# S7CAS-PLEIADES-CARTE-MERE_Pxx_CAN.net
KiCad netlist of a schematic drawn in Altium Designer
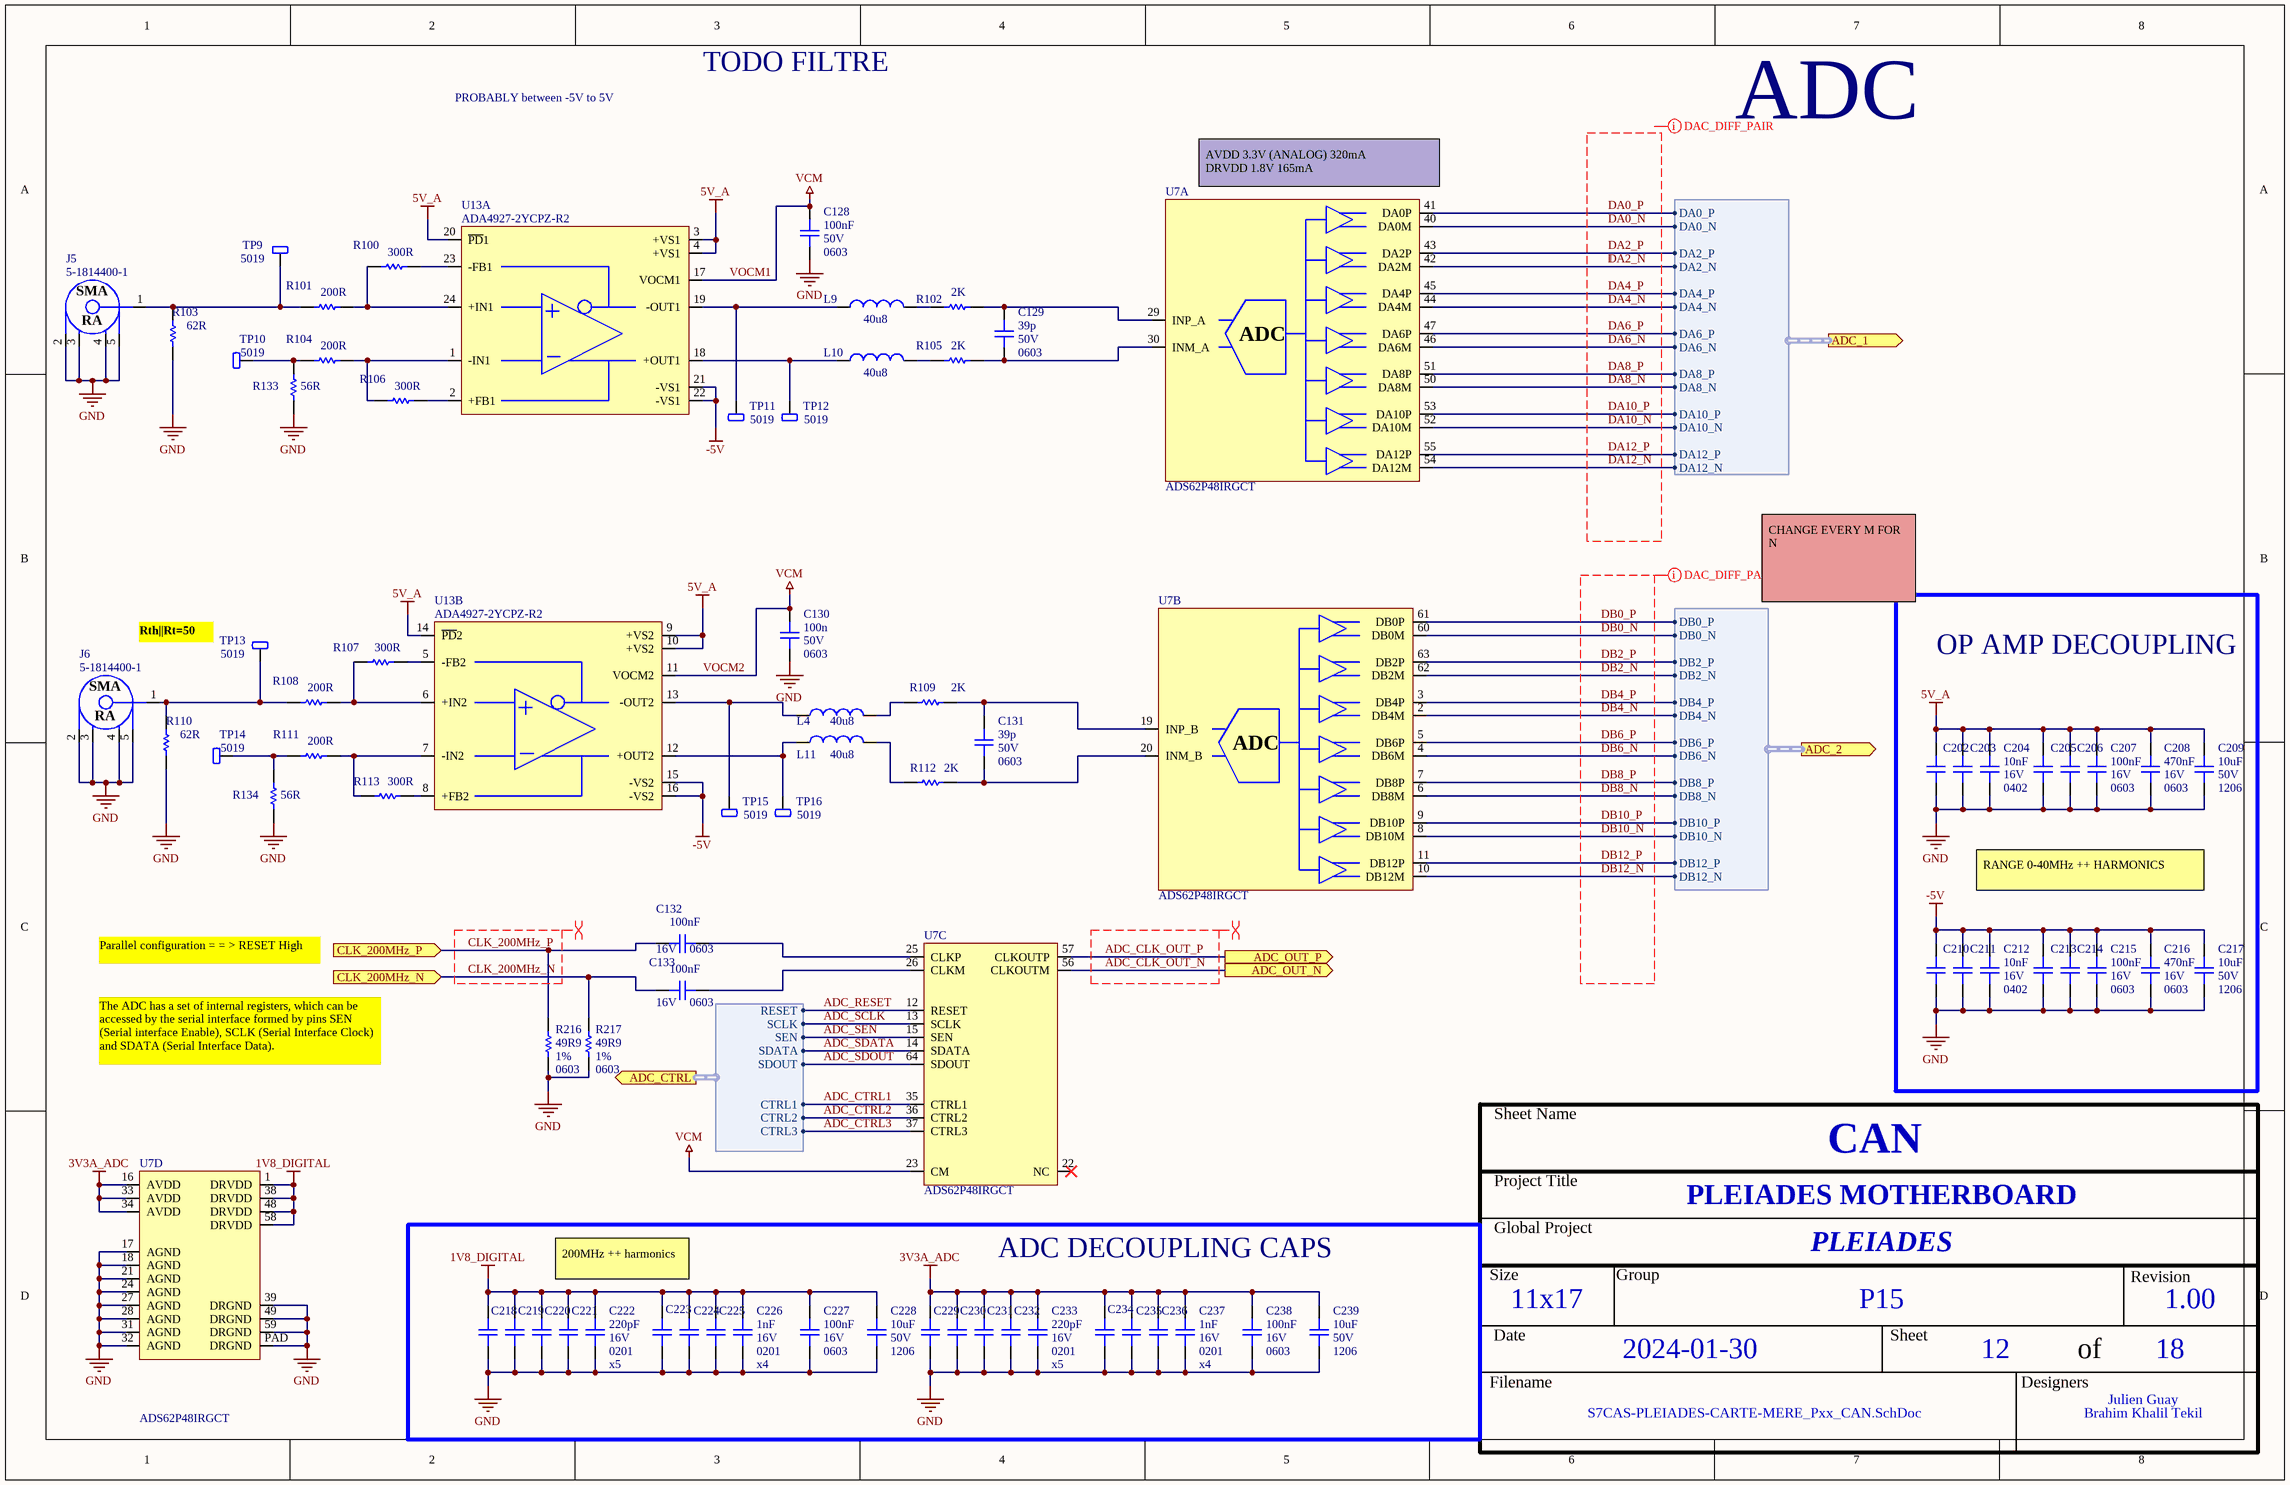
[diagram p0: S7CAS-PLEIADES-CARTE-MERE_Pxx_CAN.SchDoc]

(export (version "E")
  (design (tool "Eeschema 10.0.6"))
  (components
    (comp (ref "C128")
      (value "100nF")
      (footprint "CAP_0603")
      (description "CAP - 0603")
      (fields
        (field (name "VOLTAGE") "50V")
        (field (name "PACKAGE") "0603")
        (field (name "CREATEDBY") "Jonathan Bouchard")
      )
      (libsource (lib "S7CAS_LIB2023") (part "CAP - 0603"))
    )
    (comp (ref "C129")
      (value "39p")
      (footprint "CAP_0603")
      (description "CAP - 0603")
      (fields
        (field (name "VOLTAGE") "50V")
        (field (name "PACKAGE") "0603")
        (field (name "CREATEDBY") "Jonathan Bouchard")
      )
      (libsource (lib "S7CAS_LIB2023") (part "CAP - 0603"))
    )
    (comp (ref "C130")
      (value "100n")
      (footprint "CAP_0603")
      (description "CAP - 0603")
      (fields
        (field (name "VOLTAGE") "50V")
        (field (name "PACKAGE") "0603")
        (field (name "CREATEDBY") "Jonathan Bouchard")
      )
      (libsource (lib "S7CAS_LIB2023") (part "CAP - 0603"))
    )
    (comp (ref "C131")
      (value "39p")
      (footprint "CAP_0603")
      (description "CAP - 0603")
      (fields
        (field (name "VOLTAGE") "50V")
        (field (name "PACKAGE") "0603")
        (field (name "CREATEDBY") "Jonathan Bouchard")
      )
      (libsource (lib "S7CAS_LIB2023") (part "CAP - 0603"))
    )
    (comp (ref "C132")
      (value "100nF")
      (footprint "CAP_0603")
      (description "CAP - 0603")
      (fields
        (field (name "VOLTAGE") "16V")
        (field (name "PACKAGE") "0603")
        (field (name "CREATEDBY") "Jonathan Bouchard")
      )
      (libsource (lib "S7CAS_LIB2023") (part "CAP - 0603"))
    )
    (comp (ref "C133")
      (value "100nF")
      (footprint "CAP_0603")
      (description "CAP - 0603")
      (fields
        (field (name "VOLTAGE") "16V")
        (field (name "PACKAGE") "0603")
        (field (name "CREATEDBY") "Jonathan Bouchard")
      )
      (libsource (lib "S7CAS_LIB2023") (part "CAP - 0603"))
    )
    (comp (ref "C202")
      (value "CAP - 0402")
      (footprint "CAP_0402")
      (fields (field (name "VOLTAGE") "16V") (field (name "CREATEDBY") "Jonathan Bouchard"))
      (libsource (lib "S7CAS_LIB2023") (part "CAP - 0402"))
    )
    (comp (ref "C203")
      (value "CAP - 0402")
      (footprint "CAP_0402")
      (fields (field (name "VOLTAGE") "16V") (field (name "CREATEDBY") "Jonathan Bouchard"))
      (libsource (lib "S7CAS_LIB2023") (part "CAP - 0402"))
    )
    (comp (ref "C204")
      (value "10nF")
      (footprint "CAP_0402")
      (description "CAP - 0402")
      (fields
        (field (name "VOLTAGE") "16V")
        (field (name "PACKAGE") "0402")
        (field (name "CREATEDBY") "Jonathan Bouchard")
      )
      (libsource (lib "S7CAS_LIB2023") (part "CAP - 0402"))
    )
    (comp (ref "C205")
      (value "CAP - 0603")
      (footprint "CAP_0603")
      (fields (field (name "VOLTAGE") "16V") (field (name "CREATEDBY") "Jonathan Bouchard"))
      (libsource (lib "S7CAS_LIB2023") (part "CAP - 0603"))
    )
    (comp (ref "C206")
      (value "CAP - 0603")
      (footprint "CAP_0603")
      (fields (field (name "VOLTAGE") "16V") (field (name "CREATEDBY") "Jonathan Bouchard"))
      (libsource (lib "S7CAS_LIB2023") (part "CAP - 0603"))
    )
    (comp (ref "C207")
      (value "100nF")
      (footprint "CAP_0603")
      (description "CAP - 0603")
      (fields
        (field (name "VOLTAGE") "16V")
        (field (name "PACKAGE") "0603")
        (field (name "CREATEDBY") "Jonathan Bouchard")
      )
      (libsource (lib "S7CAS_LIB2023") (part "CAP - 0603"))
    )
    (comp (ref "C208")
      (value "470nF")
      (footprint "CAP_0603")
      (description "CAP - 0603")
      (fields
        (field (name "VOLTAGE") "16V")
        (field (name "PACKAGE") "0603")
        (field (name "CREATEDBY") "Jonathan Bouchard")
      )
      (libsource (lib "S7CAS_LIB2023") (part "CAP - 0603"))
    )
    (comp (ref "C209")
      (value "10uF")
      (footprint "CAP_1206")
      (description "CAP - 1206")
      (fields
        (field (name "VOLTAGE") "50V")
        (field (name "PACKAGE") "1206")
        (field (name "CREATEDBY") "Jonathan Bouchard")
      )
      (libsource (lib "S7CAS_LIB2023") (part "CAP - 1206"))
    )
    (comp (ref "C210")
      (value "CAP - 0402")
      (footprint "CAP_0402")
      (fields (field (name "VOLTAGE") "16V") (field (name "CREATEDBY") "Jonathan Bouchard"))
      (libsource (lib "S7CAS_LIB2023") (part "CAP - 0402"))
    )
    (comp (ref "C211")
      (value "CAP - 0402")
      (footprint "CAP_0402")
      (fields (field (name "VOLTAGE") "16V") (field (name "CREATEDBY") "Jonathan Bouchard"))
      (libsource (lib "S7CAS_LIB2023") (part "CAP - 0402"))
    )
    (comp (ref "C212")
      (value "10nF")
      (footprint "CAP_0402")
      (description "CAP - 0402")
      (fields
        (field (name "VOLTAGE") "16V")
        (field (name "PACKAGE") "0402")
        (field (name "CREATEDBY") "Jonathan Bouchard")
      )
      (libsource (lib "S7CAS_LIB2023") (part "CAP - 0402"))
    )
    (comp (ref "C213")
      (value "CAP - 0603")
      (footprint "CAP_0603")
      (fields (field (name "VOLTAGE") "16V") (field (name "CREATEDBY") "Jonathan Bouchard"))
      (libsource (lib "S7CAS_LIB2023") (part "CAP - 0603"))
    )
    (comp (ref "C214")
      (value "CAP - 0603")
      (footprint "CAP_0603")
      (fields (field (name "VOLTAGE") "16V") (field (name "CREATEDBY") "Jonathan Bouchard"))
      (libsource (lib "S7CAS_LIB2023") (part "CAP - 0603"))
    )
    (comp (ref "C215")
      (value "100nF")
      (footprint "CAP_0603")
      (description "CAP - 0603")
      (fields
        (field (name "VOLTAGE") "16V")
        (field (name "PACKAGE") "0603")
        (field (name "CREATEDBY") "Jonathan Bouchard")
      )
      (libsource (lib "S7CAS_LIB2023") (part "CAP - 0603"))
    )
    (comp (ref "C216")
      (value "470nF")
      (footprint "CAP_0603")
      (description "CAP - 0603")
      (fields
        (field (name "VOLTAGE") "16V")
        (field (name "PACKAGE") "0603")
        (field (name "CREATEDBY") "Jonathan Bouchard")
      )
      (libsource (lib "S7CAS_LIB2023") (part "CAP - 0603"))
    )
    (comp (ref "C217")
      (value "10uF")
      (footprint "CAP_1206")
      (description "CAP - 1206")
      (fields
        (field (name "VOLTAGE") "50V")
        (field (name "PACKAGE") "1206")
        (field (name "CREATEDBY") "Jonathan Bouchard")
      )
      (libsource (lib "S7CAS_LIB2023") (part "CAP - 1206"))
    )
    (comp (ref "C218")
      (value "CAP - 0201")
      (footprint "CAP_0201")
      (fields (field (name "VOLTAGE") "16V") (field (name "CREATEDBY") "Jonathan Bouchard"))
      (libsource (lib "S7CAS_LIB2023") (part "CAP - 0201"))
    )
    (comp (ref "C219")
      (value "CAP - 0201")
      (footprint "CAP_0201")
      (fields (field (name "VOLTAGE") "16V") (field (name "CREATEDBY") "Jonathan Bouchard"))
      (libsource (lib "S7CAS_LIB2023") (part "CAP - 0201"))
    )
    (comp (ref "C220")
      (value "CAP - 0201")
      (footprint "CAP_0201")
      (fields (field (name "VOLTAGE") "16V") (field (name "CREATEDBY") "Jonathan Bouchard"))
      (libsource (lib "S7CAS_LIB2023") (part "CAP - 0201"))
    )
    (comp (ref "C221")
      (value "CAP - 0201")
      (footprint "CAP_0201")
      (fields (field (name "VOLTAGE") "16V") (field (name "CREATEDBY") "Jonathan Bouchard"))
      (libsource (lib "S7CAS_LIB2023") (part "CAP - 0201"))
    )
    (comp (ref "C222")
      (value "220pF")
      (footprint "CAP_0201")
      (description "CAP - 0201")
      (fields
        (field (name "VOLTAGE") "16V")
        (field (name "PACKAGE") "0201")
        (field (name "CREATEDBY") "Jonathan Bouchard")
      )
      (libsource (lib "S7CAS_LIB2023") (part "CAP - 0201"))
    )
    (comp (ref "C223")
      (value "CAP - 0201")
      (footprint "CAP_0201")
      (fields (field (name "VOLTAGE") "16V") (field (name "CREATEDBY") "Jonathan Bouchard"))
      (libsource (lib "S7CAS_LIB2023") (part "CAP - 0201"))
    )
    (comp (ref "C224")
      (value "CAP - 0201")
      (footprint "CAP_0201")
      (fields (field (name "VOLTAGE") "16V") (field (name "CREATEDBY") "Jonathan Bouchard"))
      (libsource (lib "S7CAS_LIB2023") (part "CAP - 0201"))
    )
    (comp (ref "C225")
      (value "CAP - 0201")
      (footprint "CAP_0201")
      (fields (field (name "VOLTAGE") "16V") (field (name "CREATEDBY") "Jonathan Bouchard"))
      (libsource (lib "S7CAS_LIB2023") (part "CAP - 0201"))
    )
    (comp (ref "C226")
      (value "1nF")
      (footprint "CAP_0201")
      (description "CAP - 0201")
      (fields
        (field (name "VOLTAGE") "16V")
        (field (name "PACKAGE") "0201")
        (field (name "CREATEDBY") "Jonathan Bouchard")
      )
      (libsource (lib "S7CAS_LIB2023") (part "CAP - 0201"))
    )
    (comp (ref "C227")
      (value "100nF")
      (footprint "CAP_0603")
      (description "CAP - 0603")
      (fields
        (field (name "VOLTAGE") "16V")
        (field (name "PACKAGE") "0603")
        (field (name "CREATEDBY") "Jonathan Bouchard")
      )
      (libsource (lib "S7CAS_LIB2023") (part "CAP - 0603"))
    )
    (comp (ref "C228")
      (value "10uF")
      (footprint "CAP_1206")
      (description "CAP - 1206")
      (fields
        (field (name "VOLTAGE") "50V")
        (field (name "PACKAGE") "1206")
        (field (name "CREATEDBY") "Jonathan Bouchard")
      )
      (libsource (lib "S7CAS_LIB2023") (part "CAP - 1206"))
    )
    (comp (ref "C229")
      (value "CAP - 0201")
      (footprint "CAP_0201")
      (fields (field (name "VOLTAGE") "16V") (field (name "CREATEDBY") "Jonathan Bouchard"))
      (libsource (lib "S7CAS_LIB2023") (part "CAP - 0201"))
    )
    (comp (ref "C230")
      (value "CAP - 0201")
      (footprint "CAP_0201")
      (fields (field (name "VOLTAGE") "16V") (field (name "CREATEDBY") "Jonathan Bouchard"))
      (libsource (lib "S7CAS_LIB2023") (part "CAP - 0201"))
    )
    (comp (ref "C231")
      (value "CAP - 0201")
      (footprint "CAP_0201")
      (fields (field (name "VOLTAGE") "16V") (field (name "CREATEDBY") "Jonathan Bouchard"))
      (libsource (lib "S7CAS_LIB2023") (part "CAP - 0201"))
    )
    (comp (ref "C232")
      (value "CAP - 0201")
      (footprint "CAP_0201")
      (fields (field (name "VOLTAGE") "16V") (field (name "CREATEDBY") "Jonathan Bouchard"))
      (libsource (lib "S7CAS_LIB2023") (part "CAP - 0201"))
    )
    (comp (ref "C233")
      (value "220pF")
      (footprint "CAP_0201")
      (description "CAP - 0201")
      (fields
        (field (name "VOLTAGE") "16V")
        (field (name "PACKAGE") "0201")
        (field (name "CREATEDBY") "Jonathan Bouchard")
      )
      (libsource (lib "S7CAS_LIB2023") (part "CAP - 0201"))
    )
    (comp (ref "C234")
      (value "CAP - 0201")
      (footprint "CAP_0201")
      (fields (field (name "VOLTAGE") "16V") (field (name "CREATEDBY") "Jonathan Bouchard"))
      (libsource (lib "S7CAS_LIB2023") (part "CAP - 0201"))
    )
    (comp (ref "C235")
      (value "CAP - 0201")
      (footprint "CAP_0201")
      (fields (field (name "VOLTAGE") "16V") (field (name "CREATEDBY") "Jonathan Bouchard"))
      (libsource (lib "S7CAS_LIB2023") (part "CAP - 0201"))
    )
    (comp (ref "C236")
      (value "CAP - 0201")
      (footprint "CAP_0201")
      (fields (field (name "VOLTAGE") "16V") (field (name "CREATEDBY") "Jonathan Bouchard"))
      (libsource (lib "S7CAS_LIB2023") (part "CAP - 0201"))
    )
    (comp (ref "C237")
      (value "1nF")
      (footprint "CAP_0201")
      (description "CAP - 0201")
      (fields
        (field (name "VOLTAGE") "16V")
        (field (name "PACKAGE") "0201")
        (field (name "CREATEDBY") "Jonathan Bouchard")
      )
      (libsource (lib "S7CAS_LIB2023") (part "CAP - 0201"))
    )
    (comp (ref "C238")
      (value "100nF")
      (footprint "CAP_0603")
      (description "CAP - 0603")
      (fields
        (field (name "VOLTAGE") "16V")
        (field (name "PACKAGE") "0603")
        (field (name "CREATEDBY") "Jonathan Bouchard")
      )
      (libsource (lib "S7CAS_LIB2023") (part "CAP - 0603"))
    )
    (comp (ref "C239")
      (value "10uF")
      (footprint "CAP_1206")
      (description "CAP - 1206")
      (fields
        (field (name "VOLTAGE") "50V")
        (field (name "PACKAGE") "1206")
        (field (name "CREATEDBY") "Jonathan Bouchard")
      )
      (libsource (lib "S7CAS_LIB2023") (part "CAP - 1206"))
    )
    (comp (ref "J5")
      (value "5-1814400-1")
      (footprint "CONN_SMA_5-1814400-1")
      (description "CONN -  SMA JACK R/A 50 OHM - TH")
      (fields
        (field (name "MFG") "TE Connectivity AMP Connectors")
        (field (name "CREATEDBY") "Jonathan Bouchard")
      )
      (libsource (lib "S7CAS_LIB2023") (part "CONN_SMA_5-1814400-1"))
    )
    (comp (ref "J6")
      (value "5-1814400-1")
      (footprint "CONN_SMA_5-1814400-1")
      (description "CONN -  SMA JACK R/A 50 OHM - TH")
      (fields
        (field (name "MFG") "TE Connectivity AMP Connectors")
        (field (name "CREATEDBY") "Jonathan Bouchard")
      )
      (libsource (lib "S7CAS_LIB2023") (part "CONN_SMA_5-1814400-1"))
    )
    (comp (ref "L4")
      (value "40u8")
      (footprint "INDUCT_0603")
      (description "INDUCTOR - 0603")
      (libsource (lib "S7CAS_LIB2023") (part "INDUCT - 0603"))
    )
    (comp (ref "L9")
      (value "40u8")
      (footprint "INDUCT_0603")
      (description "INDUCTOR - 0603")
      (libsource (lib "S7CAS_LIB2023") (part "INDUCT - 0603"))
    )
    (comp (ref "L10")
      (value "40u8")
      (footprint "INDUCT_0603")
      (description "INDUCTOR - 0603")
      (libsource (lib "S7CAS_LIB2023") (part "INDUCT - 0603"))
    )
    (comp (ref "L11")
      (value "40u8")
      (footprint "INDUCT_0603")
      (description "INDUCTOR - 0603")
      (libsource (lib "S7CAS_LIB2023") (part "INDUCT - 0603"))
    )
    (comp (ref "R100")
      (value "300R")
      (footprint "RES_0603")
      (description "RES - 0603")
      (fields (field (name "CREATEDBY") "Jonathan Bouchard"))
      (libsource (lib "S7CAS_LIB2023") (part "RES - 0603"))
    )
    (comp (ref "R101")
      (value "200R")
      (footprint "RES_0603")
      (description "RES - 0603")
      (fields (field (name "CREATEDBY") "Jonathan Bouchard"))
      (libsource (lib "S7CAS_LIB2023") (part "RES - 0603"))
    )
    (comp (ref "R102")
      (value "2K")
      (footprint "RES_0603")
      (description "RES - 0603")
      (fields (field (name "CREATEDBY") "Jonathan Bouchard"))
      (libsource (lib "S7CAS_LIB2023") (part "RES - 0603"))
    )
    (comp (ref "R103")
      (value "62R")
      (footprint "RES_0603")
      (description "RES - 0603")
      (fields (field (name "CREATEDBY") "Jonathan Bouchard"))
      (libsource (lib "S7CAS_LIB2023") (part "RES - 0603"))
    )
    (comp (ref "R104")
      (value "200R")
      (footprint "RES_0603")
      (description "RES - 0603")
      (fields (field (name "CREATEDBY") "Jonathan Bouchard"))
      (libsource (lib "S7CAS_LIB2023") (part "RES - 0603"))
    )
    (comp (ref "R105")
      (value "2K")
      (footprint "RES_0603")
      (description "RES - 0603")
      (fields (field (name "CREATEDBY") "Jonathan Bouchard"))
      (libsource (lib "S7CAS_LIB2023") (part "RES - 0603"))
    )
    (comp (ref "R106")
      (value "300R")
      (footprint "RES_0603")
      (description "RES - 0603")
      (fields (field (name "CREATEDBY") "Jonathan Bouchard"))
      (libsource (lib "S7CAS_LIB2023") (part "RES - 0603"))
    )
    (comp (ref "R107")
      (value "300R")
      (footprint "RES_0603")
      (description "RES - 0603")
      (fields (field (name "CREATEDBY") "Jonathan Bouchard"))
      (libsource (lib "S7CAS_LIB2023") (part "RES - 0603"))
    )
    (comp (ref "R108")
      (value "200R")
      (footprint "RES_0603")
      (description "RES - 0603")
      (fields (field (name "CREATEDBY") "Jonathan Bouchard"))
      (libsource (lib "S7CAS_LIB2023") (part "RES - 0603"))
    )
    (comp (ref "R109")
      (value "2K")
      (footprint "RES_0603")
      (description "RES - 0603")
      (fields (field (name "CREATEDBY") "Jonathan Bouchard"))
      (libsource (lib "S7CAS_LIB2023") (part "RES - 0603"))
    )
    (comp (ref "R110")
      (value "62R")
      (footprint "RES_0603")
      (description "RES - 0603")
      (fields (field (name "CREATEDBY") "Jonathan Bouchard"))
      (libsource (lib "S7CAS_LIB2023") (part "RES - 0603"))
    )
    (comp (ref "R111")
      (value "200R")
      (footprint "RES_0603")
      (description "RES - 0603")
      (fields (field (name "CREATEDBY") "Jonathan Bouchard"))
      (libsource (lib "S7CAS_LIB2023") (part "RES - 0603"))
    )
    (comp (ref "R112")
      (value "2K")
      (footprint "RES_0603")
      (description "RES - 0603")
      (fields (field (name "CREATEDBY") "Jonathan Bouchard"))
      (libsource (lib "S7CAS_LIB2023") (part "RES - 0603"))
    )
    (comp (ref "R113")
      (value "300R")
      (footprint "RES_0603")
      (description "RES - 0603")
      (fields (field (name "CREATEDBY") "Jonathan Bouchard"))
      (libsource (lib "S7CAS_LIB2023") (part "RES - 0603"))
    )
    (comp (ref "R133")
      (value "56R")
      (footprint "RES_0603")
      (description "RES - 0603")
      (fields (field (name "CREATEDBY") "Jonathan Bouchard"))
      (libsource (lib "S7CAS_LIB2023") (part "RES - 0603"))
    )
    (comp (ref "R134")
      (value "56R")
      (footprint "RES_0603")
      (description "RES - 0603")
      (fields (field (name "CREATEDBY") "Jonathan Bouchard"))
      (libsource (lib "S7CAS_LIB2023") (part "RES - 0603"))
    )
    (comp (ref "R216")
      (value "49R9")
      (footprint "RES_0603")
      (description "RES - 0603")
      (fields
        (field (name "PACKAGE") "0603")
        (field (name "PRECISION") "1%")
        (field (name "CREATEDBY") "Jonathan Bouchard")
      )
      (libsource (lib "S7CAS_LIB2023") (part "RES - 0603"))
    )
    (comp (ref "R217")
      (value "49R9")
      (footprint "RES_0603")
      (description "RES - 0603")
      (fields
        (field (name "PACKAGE") "0603")
        (field (name "PRECISION") "1%")
        (field (name "CREATEDBY") "Jonathan Bouchard")
      )
      (libsource (lib "S7CAS_LIB2023") (part "RES - 0603"))
    )
    (comp (ref "TP9")
      (value "5019")
      (footprint "TPO_SMD_5019")
      (description "TPO - PC TEST POINT MINI - SMD")
      (fields
        (field (name "CREATEDBY/DATE") "Olivier Bernard / 5/12/2017")
        (field (name "VERIFIEDBY") "Caroline Paulin / 5 juillet 2018")
      )
      (libsource (lib "S7CAS_LIB2023") (part "TPO_SMD_5019"))
    )
    (comp (ref "TP10")
      (value "5019")
      (footprint "TPO_SMD_5019")
      (description "TPO - PC TEST POINT MINI - SMD")
      (fields
        (field (name "CREATEDBY/DATE") "Olivier Bernard / 5/12/2017")
        (field (name "VERIFIEDBY") "Caroline Paulin / 5 juillet 2018")
      )
      (libsource (lib "S7CAS_LIB2023") (part "TPO_SMD_5019"))
    )
    (comp (ref "TP11")
      (value "5019")
      (footprint "TPO_SMD_5019")
      (description "TPO - PC TEST POINT MINI - SMD")
      (fields
        (field (name "CREATEDBY/DATE") "Olivier Bernard / 5/12/2017")
        (field (name "VERIFIEDBY") "Caroline Paulin / 5 juillet 2018")
      )
      (libsource (lib "S7CAS_LIB2023") (part "TPO_SMD_5019"))
    )
    (comp (ref "TP12")
      (value "5019")
      (footprint "TPO_SMD_5019")
      (description "TPO - PC TEST POINT MINI - SMD")
      (fields
        (field (name "CREATEDBY/DATE") "Olivier Bernard / 5/12/2017")
        (field (name "VERIFIEDBY") "Caroline Paulin / 5 juillet 2018")
      )
      (libsource (lib "S7CAS_LIB2023") (part "TPO_SMD_5019"))
    )
    (comp (ref "TP13")
      (value "5019")
      (footprint "TPO_SMD_5019")
      (description "TPO - PC TEST POINT MINI - SMD")
      (fields
        (field (name "CREATEDBY/DATE") "Olivier Bernard / 5/12/2017")
        (field (name "VERIFIEDBY") "Caroline Paulin / 5 juillet 2018")
      )
      (libsource (lib "S7CAS_LIB2023") (part "TPO_SMD_5019"))
    )
    (comp (ref "TP14")
      (value "5019")
      (footprint "TPO_SMD_5019")
      (description "TPO - PC TEST POINT MINI - SMD")
      (fields
        (field (name "CREATEDBY/DATE") "Olivier Bernard / 5/12/2017")
        (field (name "VERIFIEDBY") "Caroline Paulin / 5 juillet 2018")
      )
      (libsource (lib "S7CAS_LIB2023") (part "TPO_SMD_5019"))
    )
    (comp (ref "TP15")
      (value "5019")
      (footprint "TPO_SMD_5019")
      (description "TPO - PC TEST POINT MINI - SMD")
      (fields
        (field (name "CREATEDBY/DATE") "Olivier Bernard / 5/12/2017")
        (field (name "VERIFIEDBY") "Caroline Paulin / 5 juillet 2018")
      )
      (libsource (lib "S7CAS_LIB2023") (part "TPO_SMD_5019"))
    )
    (comp (ref "TP16")
      (value "5019")
      (footprint "TPO_SMD_5019")
      (description "TPO - PC TEST POINT MINI - SMD")
      (fields
        (field (name "CREATEDBY/DATE") "Olivier Bernard / 5/12/2017")
        (field (name "VERIFIEDBY") "Caroline Paulin / 5 juillet 2018")
      )
      (libsource (lib "S7CAS_LIB2023") (part "TPO_SMD_5019"))
    )
    (comp (ref "U7")
      (value "ADS62P48IRGCT")
      (footprint "ADC_ADS62P48IRGCT")
      (description "ADC - 14 BIT 210MSPS SUAL - VQFN-64")
      (fields
        (field (name "VOLTAGE") "3.15 V ~ 3.6 V / 1.7 V ~ 1.9 V")
        (field (name "MFG") "Texas Instruments")
        (field (name "CREATEDBY") "Jonathan Bouchard")
      )
      (libsource (lib "S7CAS_LIB2023") (part "ADC_ADS62P48IRGCT"))
    )
    (comp (ref "U13")
      (value "ADA4927-2YCPZ-R2")
      (footprint "OPAMP_ADA4927-2YCPZ-R2")
      (description "OPAMP - CFA 2.3GHZ - QFN-24")
      (fields
        (field (name "VOLTAGE") "4.5 V ~ 11 V, ±2.25 V ~ 5.5 V")
        (field (name "MFG") "Analog Devices")
        (field (name "CREATEDBY") "Jonathan Bouchard")
      )
      (libsource (lib "S7CAS_LIB2023") (part "OPAMP_ADA4927-2YCPZ-R2"))
    )
  )
  (nets
    (net (code "4") (name "-5V") (class "Default")
      (node (ref "C210") (pin "2") (pinfunction "2_2") (pintype "passive"))
      (node (ref "C211") (pin "2") (pinfunction "2_2") (pintype "passive"))
      (node (ref "C212") (pin "2") (pinfunction "2_2") (pintype "passive"))
      (node (ref "C213") (pin "2") (pinfunction "2_2") (pintype "passive"))
      (node (ref "C214") (pin "2") (pinfunction "2_2") (pintype "passive"))
      (node (ref "C215") (pin "2") (pinfunction "2_2") (pintype "passive"))
      (node (ref "C216") (pin "2") (pinfunction "2_2") (pintype "passive"))
      (node (ref "C217") (pin "2") (pinfunction "2_2") (pintype "passive"))
      (node (ref "U13") (pin "15") (pinfunction "-VS2_15") (pintype "passive"))
      (node (ref "U13") (pin "16") (pinfunction "-VS2_16") (pintype "passive"))
      (node (ref "U13") (pin "21") (pinfunction "-VS1_21") (pintype "passive"))
      (node (ref "U13") (pin "22") (pinfunction "-VS1_22") (pintype "passive"))
    )
    (net (code "5") (name "/") (class "Default")
      (node (ref "U7") (pin "42") (pinfunction "DA2M_42") (pintype "passive"))
    )
    (net (code "6") (name "/ADC_CLK_OUT_N") (class "Default")
      (node (ref "U7") (pin "56") (pinfunction "CLKOUTM_56") (pintype "passive"))
    )
    (net (code "7") (name "/ADC_CLK_OUT_P") (class "Default")
      (node (ref "U7") (pin "57") (pinfunction "CLKOUTP_57") (pintype "passive"))
    )
    (net (code "8") (name "/ADC_CTRL1") (class "Default")
      (node (ref "U7") (pin "35") (pinfunction "CTRL1_35") (pintype "passive"))
    )
    (net (code "9") (name "/ADC_CTRL2") (class "Default")
      (node (ref "U7") (pin "36") (pinfunction "CTRL2_36") (pintype "passive"))
    )
    (net (code "10") (name "/ADC_CTRL3") (class "Default")
      (node (ref "U7") (pin "37") (pinfunction "CTRL3_37") (pintype "passive"))
    )
    (net (code "11") (name "/ADC_RESET") (class "Default")
      (node (ref "U7") (pin "12") (pinfunction "RESET_12") (pintype "passive"))
    )
    (net (code "12") (name "/ADC_SCLK") (class "Default")
      (node (ref "U7") (pin "13") (pinfunction "SCLK_13") (pintype "passive"))
    )
    (net (code "13") (name "/ADC_SDATA") (class "Default")
      (node (ref "U7") (pin "14") (pinfunction "SDATA_14") (pintype "passive"))
    )
    (net (code "14") (name "/ADC_SDOUT") (class "Default")
      (node (ref "U7") (pin "64") (pinfunction "SDOUT_64") (pintype "passive"))
    )
    (net (code "15") (name "/ADC_SEN") (class "Default")
      (node (ref "U7") (pin "15") (pinfunction "SEN_15") (pintype "passive"))
    )
    (net (code "16") (name "/CLK_200MHz_N") (class "Default")
      (node (ref "C133") (pin "2") (pinfunction "2_2") (pintype "passive"))
      (node (ref "R217") (pin "2") (pinfunction "2_2") (pintype "passive"))
    )
    (net (code "17") (name "/CLK_200MHz_P") (class "Default")
      (node (ref "C132") (pin "2") (pinfunction "2_2") (pintype "passive"))
      (node (ref "R216") (pin "2") (pinfunction "2_2") (pintype "passive"))
    )
    (net (code "18") (name "/DA0_N") (class "Default")
      (node (ref "U7") (pin "40") (pinfunction "DA0M_40") (pintype "passive"))
    )
    (net (code "19") (name "/DA0_P") (class "Default")
      (node (ref "U7") (pin "41") (pinfunction "DA0P_41") (pintype "passive"))
    )
    (net (code "20") (name "/DA2_P") (class "Default")
      (node (ref "U7") (pin "43") (pinfunction "DA2P_43") (pintype "passive"))
    )
    (net (code "21") (name "/DA4_N") (class "Default")
      (node (ref "U7") (pin "44") (pinfunction "DA4M_44") (pintype "passive"))
    )
    (net (code "22") (name "/DA4_P") (class "Default")
      (node (ref "U7") (pin "45") (pinfunction "DA4P_45") (pintype "passive"))
    )
    (net (code "23") (name "/DA6_N") (class "Default")
      (node (ref "U7") (pin "46") (pinfunction "DA6M_46") (pintype "passive"))
    )
    (net (code "24") (name "/DA6_P") (class "Default")
      (node (ref "U7") (pin "47") (pinfunction "DA6P_47") (pintype "passive"))
    )
    (net (code "25") (name "/DA8_N") (class "Default")
      (node (ref "U7") (pin "50") (pinfunction "DA8M_50") (pintype "passive"))
    )
    (net (code "26") (name "/DA8_P") (class "Default")
      (node (ref "U7") (pin "51") (pinfunction "DA8P_51") (pintype "passive"))
    )
    (net (code "27") (name "/DA10_N") (class "Default")
      (node (ref "U7") (pin "52") (pinfunction "DA10M_52") (pintype "passive"))
    )
    (net (code "28") (name "/DA10_P") (class "Default")
      (node (ref "U7") (pin "53") (pinfunction "DA10P_53") (pintype "passive"))
    )
    (net (code "29") (name "/DA12_N") (class "Default")
      (node (ref "U7") (pin "54") (pinfunction "DA12M_54") (pintype "passive"))
    )
    (net (code "30") (name "/DA12_P") (class "Default")
      (node (ref "U7") (pin "55") (pinfunction "DA12P_55") (pintype "passive"))
    )
    (net (code "31") (name "/DB0_N") (class "Default")
      (node (ref "U7") (pin "60") (pinfunction "DB0M_60") (pintype "passive"))
    )
    (net (code "32") (name "/DB0_P") (class "Default")
      (node (ref "U7") (pin "61") (pinfunction "DB0P_61") (pintype "passive"))
    )
    (net (code "33") (name "/DB2_N") (class "Default")
      (node (ref "U7") (pin "62") (pinfunction "DB2M_62") (pintype "passive"))
    )
    (net (code "34") (name "/DB2_P") (class "Default")
      (node (ref "U7") (pin "63") (pinfunction "DB2P_63") (pintype "passive"))
    )
    (net (code "35") (name "/DB4_N") (class "Default")
      (node (ref "U7") (pin "2") (pinfunction "DB4M_2") (pintype "passive"))
    )
    (net (code "36") (name "/DB4_P") (class "Default")
      (node (ref "U7") (pin "3") (pinfunction "DB4P_3") (pintype "passive"))
    )
    (net (code "37") (name "/DB6_N") (class "Default")
      (node (ref "U7") (pin "4") (pinfunction "DB6M_4") (pintype "passive"))
    )
    (net (code "38") (name "/DB6_P") (class "Default")
      (node (ref "U7") (pin "5") (pinfunction "DB6P_5") (pintype "passive"))
    )
    (net (code "39") (name "/DB8_N") (class "Default")
      (node (ref "U7") (pin "6") (pinfunction "DB8M_6") (pintype "passive"))
    )
    (net (code "40") (name "/DB8_P") (class "Default")
      (node (ref "U7") (pin "7") (pinfunction "DB8P_7") (pintype "passive"))
    )
    (net (code "41") (name "/DB10_N") (class "Default")
      (node (ref "U7") (pin "8") (pinfunction "DB10M_8") (pintype "passive"))
    )
    (net (code "42") (name "/DB10_P") (class "Default")
      (node (ref "U7") (pin "9") (pinfunction "DB10P_9") (pintype "passive"))
    )
    (net (code "43") (name "/DB12_N") (class "Default")
      (node (ref "U7") (pin "10") (pinfunction "DB12M_10") (pintype "passive"))
    )
    (net (code "44") (name "/DB12_P") (class "Default")
      (node (ref "U7") (pin "11") (pinfunction "DB12P_11") (pintype "passive"))
    )
    (net (code "48") (name "1V8_DIGITAL") (class "Default")
      (node (ref "C218") (pin "2") (pinfunction "2_2") (pintype "passive"))
      (node (ref "C219") (pin "2") (pinfunction "2_2") (pintype "passive"))
      (node (ref "C220") (pin "2") (pinfunction "2_2") (pintype "passive"))
      (node (ref "C221") (pin "2") (pinfunction "2_2") (pintype "passive"))
      (node (ref "C222") (pin "2") (pinfunction "2_2") (pintype "passive"))
      (node (ref "C223") (pin "2") (pinfunction "2_2") (pintype "passive"))
      (node (ref "C224") (pin "2") (pinfunction "2_2") (pintype "passive"))
      (node (ref "C225") (pin "2") (pinfunction "2_2") (pintype "passive"))
      (node (ref "C226") (pin "2") (pinfunction "2_2") (pintype "passive"))
      (node (ref "C227") (pin "2") (pinfunction "2_2") (pintype "passive"))
      (node (ref "C228") (pin "2") (pinfunction "2_2") (pintype "passive"))
      (node (ref "U7") (pin "1") (pinfunction "DRVDD_1") (pintype "passive"))
      (node (ref "U7") (pin "38") (pinfunction "DRVDD_38") (pintype "passive"))
      (node (ref "U7") (pin "48") (pinfunction "DRVDD_48") (pintype "passive"))
      (node (ref "U7") (pin "58") (pinfunction "DRVDD_58") (pintype "passive"))
    )
    (net (code "49") (name "3V3A_ADC") (class "Default")
      (node (ref "C229") (pin "2") (pinfunction "2_2") (pintype "passive"))
      (node (ref "C230") (pin "2") (pinfunction "2_2") (pintype "passive"))
      (node (ref "C231") (pin "2") (pinfunction "2_2") (pintype "passive"))
      (node (ref "C232") (pin "2") (pinfunction "2_2") (pintype "passive"))
      (node (ref "C233") (pin "2") (pinfunction "2_2") (pintype "passive"))
      (node (ref "C234") (pin "2") (pinfunction "2_2") (pintype "passive"))
      (node (ref "C235") (pin "2") (pinfunction "2_2") (pintype "passive"))
      (node (ref "C236") (pin "2") (pinfunction "2_2") (pintype "passive"))
      (node (ref "C237") (pin "2") (pinfunction "2_2") (pintype "passive"))
      (node (ref "C238") (pin "2") (pinfunction "2_2") (pintype "passive"))
      (node (ref "C239") (pin "2") (pinfunction "2_2") (pintype "passive"))
      (node (ref "U7") (pin "16") (pinfunction "AVDD_16") (pintype "passive"))
      (node (ref "U7") (pin "33") (pinfunction "AVDD_33") (pintype "passive"))
      (node (ref "U7") (pin "34") (pinfunction "AVDD_34") (pintype "passive"))
    )
    (net (code "50") (name "5V_A") (class "Default")
      (node (ref "C202") (pin "2") (pinfunction "2_2") (pintype "passive"))
      (node (ref "C203") (pin "2") (pinfunction "2_2") (pintype "passive"))
      (node (ref "C204") (pin "2") (pinfunction "2_2") (pintype "passive"))
      (node (ref "C205") (pin "2") (pinfunction "2_2") (pintype "passive"))
      (node (ref "C206") (pin "2") (pinfunction "2_2") (pintype "passive"))
      (node (ref "C207") (pin "2") (pinfunction "2_2") (pintype "passive"))
      (node (ref "C208") (pin "2") (pinfunction "2_2") (pintype "passive"))
      (node (ref "C209") (pin "2") (pinfunction "2_2") (pintype "passive"))
      (node (ref "U13") (pin "10") (pinfunction "+VS2_10") (pintype "passive"))
      (node (ref "U13") (pin "14") (pinfunction "~{PD}2_14") (pintype "passive"))
      (node (ref "U13") (pin "20") (pinfunction "~{PD}1_20") (pintype "passive"))
      (node (ref "U13") (pin "3") (pinfunction "+VS1_3") (pintype "passive"))
      (node (ref "U13") (pin "4") (pinfunction "+VS1_4") (pintype "passive"))
      (node (ref "U13") (pin "9") (pinfunction "+VS2_9") (pintype "passive"))
    )
    (net (code "51") (name "GND") (class "Default")
      (node (ref "C128") (pin "1") (pinfunction "1_1") (pintype "passive"))
      (node (ref "C130") (pin "1") (pinfunction "1_1") (pintype "passive"))
      (node (ref "C202") (pin "1") (pinfunction "1_1") (pintype "passive"))
      (node (ref "C203") (pin "1") (pinfunction "1_1") (pintype "passive"))
      (node (ref "C204") (pin "1") (pinfunction "1_1") (pintype "passive"))
      (node (ref "C205") (pin "1") (pinfunction "1_1") (pintype "passive"))
      (node (ref "C206") (pin "1") (pinfunction "1_1") (pintype "passive"))
      (node (ref "C207") (pin "1") (pinfunction "1_1") (pintype "passive"))
      (node (ref "C208") (pin "1") (pinfunction "1_1") (pintype "passive"))
      (node (ref "C209") (pin "1") (pinfunction "1_1") (pintype "passive"))
      (node (ref "C210") (pin "1") (pinfunction "1_1") (pintype "passive"))
      (node (ref "C211") (pin "1") (pinfunction "1_1") (pintype "passive"))
      (node (ref "C212") (pin "1") (pinfunction "1_1") (pintype "passive"))
      (node (ref "C213") (pin "1") (pinfunction "1_1") (pintype "passive"))
      (node (ref "C214") (pin "1") (pinfunction "1_1") (pintype "passive"))
      (node (ref "C215") (pin "1") (pinfunction "1_1") (pintype "passive"))
      (node (ref "C216") (pin "1") (pinfunction "1_1") (pintype "passive"))
      (node (ref "C217") (pin "1") (pinfunction "1_1") (pintype "passive"))
      (node (ref "C218") (pin "1") (pinfunction "1_1") (pintype "passive"))
      (node (ref "C219") (pin "1") (pinfunction "1_1") (pintype "passive"))
      (node (ref "C220") (pin "1") (pinfunction "1_1") (pintype "passive"))
      (node (ref "C221") (pin "1") (pinfunction "1_1") (pintype "passive"))
      (node (ref "C222") (pin "1") (pinfunction "1_1") (pintype "passive"))
      (node (ref "C223") (pin "1") (pinfunction "1_1") (pintype "passive"))
      (node (ref "C224") (pin "1") (pinfunction "1_1") (pintype "passive"))
      (node (ref "C225") (pin "1") (pinfunction "1_1") (pintype "passive"))
      (node (ref "C226") (pin "1") (pinfunction "1_1") (pintype "passive"))
      (node (ref "C227") (pin "1") (pinfunction "1_1") (pintype "passive"))
      (node (ref "C228") (pin "1") (pinfunction "1_1") (pintype "passive"))
      (node (ref "C229") (pin "1") (pinfunction "1_1") (pintype "passive"))
      (node (ref "C230") (pin "1") (pinfunction "1_1") (pintype "passive"))
      (node (ref "C231") (pin "1") (pinfunction "1_1") (pintype "passive"))
      (node (ref "C232") (pin "1") (pinfunction "1_1") (pintype "passive"))
      (node (ref "C233") (pin "1") (pinfunction "1_1") (pintype "passive"))
      (node (ref "C234") (pin "1") (pinfunction "1_1") (pintype "passive"))
      (node (ref "C235") (pin "1") (pinfunction "1_1") (pintype "passive"))
      (node (ref "C236") (pin "1") (pinfunction "1_1") (pintype "passive"))
      (node (ref "C237") (pin "1") (pinfunction "1_1") (pintype "passive"))
      (node (ref "C238") (pin "1") (pinfunction "1_1") (pintype "passive"))
      (node (ref "C239") (pin "1") (pinfunction "1_1") (pintype "passive"))
      (node (ref "J5") (pin "2") (pinfunction "2_2") (pintype "passive"))
      (node (ref "J5") (pin "3") (pinfunction "3_3") (pintype "passive"))
      (node (ref "J5") (pin "4") (pinfunction "4_4") (pintype "passive"))
      (node (ref "J5") (pin "5") (pinfunction "5_5") (pintype "passive"))
      (node (ref "J6") (pin "2") (pinfunction "2_2") (pintype "passive"))
      (node (ref "J6") (pin "3") (pinfunction "3_3") (pintype "passive"))
      (node (ref "J6") (pin "4") (pinfunction "4_4") (pintype "passive"))
      (node (ref "J6") (pin "5") (pinfunction "5_5") (pintype "passive"))
      (node (ref "R103") (pin "1") (pinfunction "1_1") (pintype "passive"))
      (node (ref "R110") (pin "1") (pinfunction "1_1") (pintype "passive"))
      (node (ref "R133") (pin "2") (pinfunction "2_2") (pintype "passive"))
      (node (ref "R134") (pin "2") (pinfunction "2_2") (pintype "passive"))
      (node (ref "R216") (pin "1") (pinfunction "1_1") (pintype "passive"))
      (node (ref "R217") (pin "1") (pinfunction "1_1") (pintype "passive"))
      (node (ref "U7") (pin "17") (pinfunction "AGND_17") (pintype "passive"))
      (node (ref "U7") (pin "18") (pinfunction "AGND_18") (pintype "passive"))
      (node (ref "U7") (pin "21") (pinfunction "AGND_21") (pintype "passive"))
      (node (ref "U7") (pin "24") (pinfunction "AGND_24") (pintype "passive"))
      (node (ref "U7") (pin "27") (pinfunction "AGND_27") (pintype "passive"))
      (node (ref "U7") (pin "28") (pinfunction "AGND_28") (pintype "passive"))
      (node (ref "U7") (pin "31") (pinfunction "AGND_31") (pintype "passive"))
      (node (ref "U7") (pin "32") (pinfunction "AGND_32") (pintype "passive"))
      (node (ref "U7") (pin "39") (pinfunction "DRGND_39") (pintype "passive"))
      (node (ref "U7") (pin "49") (pinfunction "DRGND_49") (pintype "passive"))
      (node (ref "U7") (pin "59") (pinfunction "DRGND_59") (pintype "passive"))
      (node (ref "U7") (pin "PAD") (pinfunction "DRGND_PAD") (pintype "passive"))
    )
    (net (code "52") (name "Net-(J5-Pad1)") (class "Default")
      (node (ref "J5") (pin "1") (pinfunction "1_1") (pintype "passive"))
      (node (ref "R101") (pin "2") (pinfunction "2_2") (pintype "passive"))
      (node (ref "R103") (pin "2") (pinfunction "2_2") (pintype "passive"))
      (node (ref "TP9") (pin "1") (pinfunction "1_1") (pintype "passive"))
    )
    (net (code "53") (name "Net-(J6-Pad1)") (class "Default")
      (node (ref "J6") (pin "1") (pinfunction "1_1") (pintype "passive"))
      (node (ref "R108") (pin "2") (pinfunction "2_2") (pintype "passive"))
      (node (ref "R110") (pin "2") (pinfunction "2_2") (pintype "passive"))
      (node (ref "TP13") (pin "1") (pinfunction "1_1") (pintype "passive"))
    )
    (net (code "54") (name "Net-(L4-Pad2)") (class "Default")
      (node (ref "L4") (pin "2") (pinfunction "2_2") (pintype "passive"))
      (node (ref "R109") (pin "2") (pinfunction "2_2") (pintype "passive"))
    )
    (net (code "55") (name "Net-(L9-Pad2)") (class "Default")
      (node (ref "L9") (pin "2") (pinfunction "2_2") (pintype "passive"))
      (node (ref "R102") (pin "2") (pinfunction "2_2") (pintype "passive"))
    )
    (net (code "56") (name "Net-(L10-Pad2)") (class "Default")
      (node (ref "L10") (pin "2") (pinfunction "2_2") (pintype "passive"))
      (node (ref "R105") (pin "2") (pinfunction "2_2") (pintype "passive"))
    )
    (net (code "57") (name "Net-(L11-Pad2)") (class "Default")
      (node (ref "L11") (pin "2") (pinfunction "2_2") (pintype "passive"))
      (node (ref "R112") (pin "2") (pinfunction "2_2") (pintype "passive"))
    )
    (net (code "58") (name "Net-(R104-Pad2)") (class "Default")
      (node (ref "R104") (pin "2") (pinfunction "2_2") (pintype "passive"))
      (node (ref "R133") (pin "1") (pinfunction "1_1") (pintype "passive"))
      (node (ref "TP10") (pin "1") (pinfunction "1_1") (pintype "passive"))
    )
    (net (code "59") (name "Net-(R111-Pad2)") (class "Default")
      (node (ref "R111") (pin "2") (pinfunction "2_2") (pintype "passive"))
      (node (ref "R134") (pin "1") (pinfunction "1_1") (pintype "passive"))
      (node (ref "TP14") (pin "1") (pinfunction "1_1") (pintype "passive"))
    )
    (net (code "60") (name "Net-(U7A-INM_A)") (class "Default")
      (node (ref "C129") (pin "1") (pinfunction "1_1") (pintype "passive"))
      (node (ref "R105") (pin "1") (pinfunction "1_1") (pintype "passive"))
      (node (ref "U7") (pin "30") (pinfunction "INM_A_30") (pintype "passive"))
    )
    (net (code "61") (name "Net-(U7A-INP_A)") (class "Default")
      (node (ref "C129") (pin "2") (pinfunction "2_2") (pintype "passive"))
      (node (ref "R102") (pin "1") (pinfunction "1_1") (pintype "passive"))
      (node (ref "U7") (pin "29") (pinfunction "INP_A_29") (pintype "passive"))
    )
    (net (code "62") (name "Net-(U7B-INM_B)") (class "Default")
      (node (ref "C131") (pin "1") (pinfunction "1_1") (pintype "passive"))
      (node (ref "R112") (pin "1") (pinfunction "1_1") (pintype "passive"))
      (node (ref "U7") (pin "20") (pinfunction "INM_B_20") (pintype "passive"))
    )
    (net (code "63") (name "Net-(U7B-INP_B)") (class "Default")
      (node (ref "C131") (pin "2") (pinfunction "2_2") (pintype "passive"))
      (node (ref "R109") (pin "1") (pinfunction "1_1") (pintype "passive"))
      (node (ref "U7") (pin "19") (pinfunction "INP_B_19") (pintype "passive"))
    )
    (net (code "64") (name "Net-(U7C-CLKM)") (class "Default")
      (node (ref "C133") (pin "1") (pinfunction "1_1") (pintype "passive"))
      (node (ref "U7") (pin "26") (pinfunction "CLKM_26") (pintype "passive"))
    )
    (net (code "65") (name "Net-(U7C-CLKP)") (class "Default")
      (node (ref "C132") (pin "1") (pinfunction "1_1") (pintype "passive"))
      (node (ref "U7") (pin "25") (pinfunction "CLKP_25") (pintype "passive"))
    )
    (net (code "66") (name "Net-(U13A-+FB1)") (class "Default")
      (node (ref "R106") (pin "1") (pinfunction "1_1") (pintype "passive"))
      (node (ref "U13") (pin "2") (pinfunction "+FB1_2") (pintype "passive"))
    )
    (net (code "67") (name "Net-(U13A-+IN1)") (class "Default")
      (node (ref "R100") (pin "2") (pinfunction "2_2") (pintype "passive"))
      (node (ref "R101") (pin "1") (pinfunction "1_1") (pintype "passive"))
      (node (ref "U13") (pin "24") (pinfunction "+IN1_24") (pintype "passive"))
    )
    (net (code "68") (name "Net-(U13A-+OUT1)") (class "Default")
      (node (ref "L10") (pin "1") (pinfunction "1_1") (pintype "passive"))
      (node (ref "TP12") (pin "1") (pinfunction "1_1") (pintype "passive"))
      (node (ref "U13") (pin "18") (pinfunction "+OUT1_18") (pintype "passive"))
    )
    (net (code "69") (name "Net-(U13A--FB1)") (class "Default")
      (node (ref "R100") (pin "1") (pinfunction "1_1") (pintype "passive"))
      (node (ref "U13") (pin "23") (pinfunction "-FB1_23") (pintype "passive"))
    )
    (net (code "70") (name "Net-(U13A--IN1)") (class "Default")
      (node (ref "R104") (pin "1") (pinfunction "1_1") (pintype "passive"))
      (node (ref "R106") (pin "2") (pinfunction "2_2") (pintype "passive"))
      (node (ref "U13") (pin "1") (pinfunction "-IN1_1") (pintype "passive"))
    )
    (net (code "71") (name "Net-(U13A--OUT1)") (class "Default")
      (node (ref "L9") (pin "1") (pinfunction "1_1") (pintype "passive"))
      (node (ref "TP11") (pin "1") (pinfunction "1_1") (pintype "passive"))
      (node (ref "U13") (pin "19") (pinfunction "-OUT1_19") (pintype "passive"))
    )
    (net (code "72") (name "Net-(U13B-+FB2)") (class "Default")
      (node (ref "R113") (pin "1") (pinfunction "1_1") (pintype "passive"))
      (node (ref "U13") (pin "8") (pinfunction "+FB2_8") (pintype "passive"))
    )
    (net (code "73") (name "Net-(U13B-+IN2)") (class "Default")
      (node (ref "R107") (pin "2") (pinfunction "2_2") (pintype "passive"))
      (node (ref "R108") (pin "1") (pinfunction "1_1") (pintype "passive"))
      (node (ref "U13") (pin "6") (pinfunction "+IN2_6") (pintype "passive"))
    )
    (net (code "74") (name "Net-(U13B-+OUT2)") (class "Default")
      (node (ref "L11") (pin "1") (pinfunction "1_1") (pintype "passive"))
      (node (ref "TP16") (pin "1") (pinfunction "1_1") (pintype "passive"))
      (node (ref "U13") (pin "12") (pinfunction "+OUT2_12") (pintype "passive"))
    )
    (net (code "75") (name "Net-(U13B--FB2)") (class "Default")
      (node (ref "R107") (pin "1") (pinfunction "1_1") (pintype "passive"))
      (node (ref "U13") (pin "5") (pinfunction "-FB2_5") (pintype "passive"))
    )
    (net (code "76") (name "Net-(U13B--IN2)") (class "Default")
      (node (ref "R111") (pin "1") (pinfunction "1_1") (pintype "passive"))
      (node (ref "R113") (pin "2") (pinfunction "2_2") (pintype "passive"))
      (node (ref "U13") (pin "7") (pinfunction "-IN2_7") (pintype "passive"))
    )
    (net (code "77") (name "Net-(U13B--OUT2)") (class "Default")
      (node (ref "L4") (pin "1") (pinfunction "1_1") (pintype "passive"))
      (node (ref "TP15") (pin "1") (pinfunction "1_1") (pintype "passive"))
      (node (ref "U13") (pin "13") (pinfunction "-OUT2_13") (pintype "passive"))
    )
    (net (code "78") (name "VCM") (class "Default")
      (node (ref "C128") (pin "2") (pinfunction "2_2") (pintype "passive"))
      (node (ref "C130") (pin "2") (pinfunction "2_2") (pintype "passive"))
      (node (ref "U13") (pin "11") (pinfunction "VOCM2_11") (pintype "passive"))
      (node (ref "U13") (pin "17") (pinfunction "VOCM1_17") (pintype "passive"))
      (node (ref "U7") (pin "23") (pinfunction "CM_23") (pintype "passive"))
    )
    (net (code "79") (name "unconnected-(U7C-NC-Pad22)") (class "Default")
      (node (ref "U7") (pin "22") (pinfunction "NC_22") (pintype "passive+no_connect"))
    )
  )
)
